# 1-Schematic_MicroCubeSat.net
KiCad netlist of a schematic drawn in EasyEDA
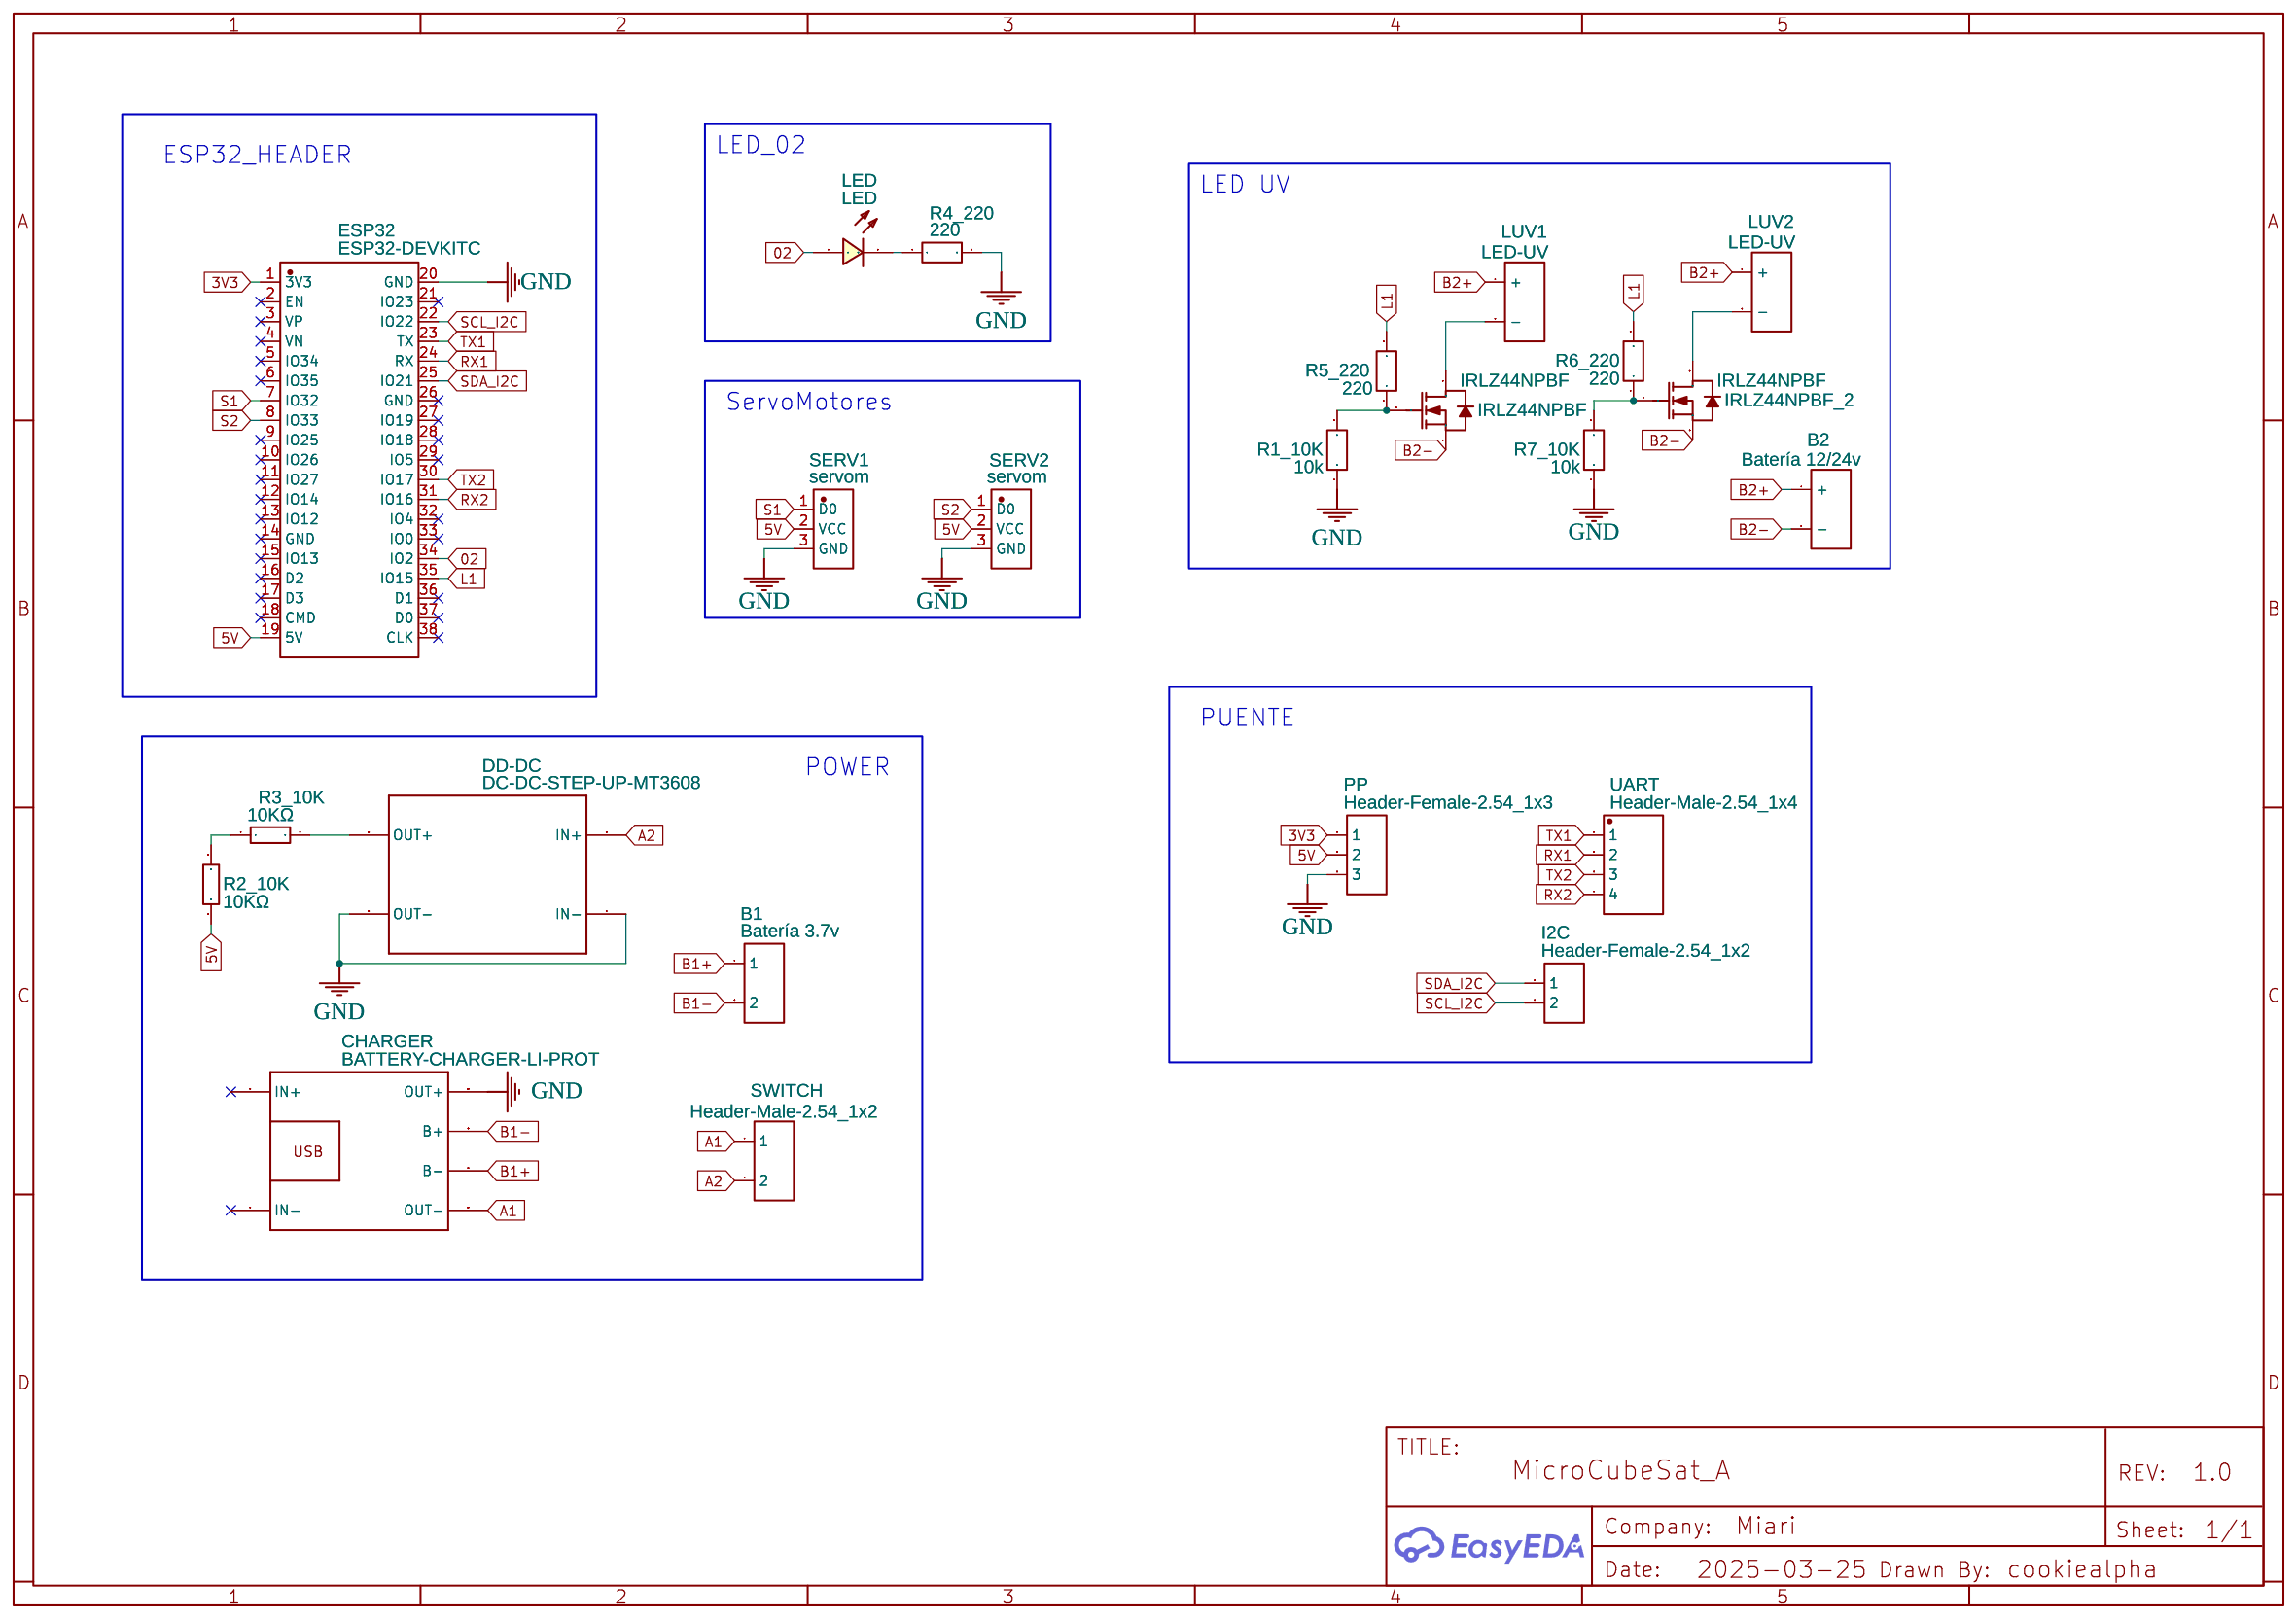
[diagram p0: schematic sheet]

(export (version "E")
  (design (tool "Eeschema 10.0.6"))
  (components
    (comp (ref "B1")
      (value "Batería 3.7v")
      (fields
        (field (name "Manufacturer Part") "826629-2")
        (field (name "Manufacturer") "TE Connectivity(泰科电子)")
      )
      (libsource (lib "") (part "Header-Male-2.54_1x2_1"))
    )
    (comp (ref "B2")
      (value "Batería 12/24v")
      (fields
        (field (name "Manufacturer Part") "826629-2")
        (field (name "Manufacturer") "TE Connectivity(泰科电子)")
      )
      (libsource (lib "") (part "Header-Male-2.54_1x2_2"))
    )
    (comp (ref "CHARGER")
      (value "BATTERY-CHARGER-LI-PROT")
      (libsource (lib "") (part "BATTERY-CHARGER-LI-PROT"))
    )
    (comp (ref "DD-DC") (value "DC-DC-STEP-UP-MT3608") (libsource (lib "") (part "DC-DC-STEP-UP-MT3608")))
    (comp (ref "ESP32")
      (value "ESP32-DEVKITC")
      (fields
        (field (name "Manufacturer Part") "ESP32-DevKitC")
        (field (name "Manufacturer") "ESPRESSIF(乐鑫)")
      )
      (libsource (lib "") (part "ESP32-DEVKITC"))
    )
    (comp (ref "I2C")
      (value "Header-Female-2.54_1x2")
      (fields (field (name "Manufacturer Part") "2.54-1*2P母") (field (name "Manufacturer") "BOOMELE(博穆精密)"))
      (libsource (lib "") (part "Header-Female-2.54_1x2"))
    )
    (comp (ref "IRLZ44NPBF")
      (value "IRLZ44NPBF")
      (fields (field (name "Manufacturer") "Infineon(英飞凌)"))
      (libsource (lib "") (part "IRLZ44NPBF_1"))
    )
    (comp (ref "IRLZ44NPBF_2")
      (value "IRLZ44NPBF")
      (fields (field (name "Manufacturer") "Infineon(英飞凌)"))
      (libsource (lib "") (part "IRLZ44NPBF"))
    )
    (comp (ref "LED")
      (value "LED")
      (fields (field (name "Manufacturer Part") "LED05-红灯"))
      (libsource (lib "") (part "LED05-红灯"))
    )
    (comp (ref "LUV1")
      (value "LED-UV")
      (fields
        (field (name "Manufacturer Part") "826629-2")
        (field (name "Manufacturer") "TE Connectivity(泰科电子)")
      )
      (libsource (lib "") (part "Header-Male-2.54_1x2"))
    )
    (comp (ref "LUV2")
      (value "LED-UV")
      (fields
        (field (name "Manufacturer Part") "826629-2")
        (field (name "Manufacturer") "TE Connectivity(泰科电子)")
      )
      (libsource (lib "") (part "Header-Male-2.54_1x2"))
    )
    (comp (ref "PP")
      (value "Header-Female-2.54_1x3")
      (fields (field (name "Manufacturer Part") "2.54-1*3P母") (field (name "Manufacturer") "BOOMELE(博穆精密)"))
      (libsource (lib "") (part "Header-Female-2.54_1x3"))
    )
    (comp (ref "R1_10K") (value "10k") (libsource (lib "") (part "ResistorAxial1/2wLHoles13.89mm_1")))
    (comp (ref "R2_10K")
      (value "10KΩ")
      (fields
        (field (name "Manufacturer Part") "MF58 103J3470")
        (field (name "Manufacturer") "Nanjing Shiheng Elec")
      )
      (libsource (lib "") (part "RESISTANCE_10k_1"))
    )
    (comp (ref "R3_10K")
      (value "10KΩ")
      (fields
        (field (name "Manufacturer Part") "MF58 103J3470")
        (field (name "Manufacturer") "Nanjing Shiheng Elec")
      )
      (libsource (lib "") (part "RESISTANCE_10k"))
    )
    (comp (ref "R4_220") (value "220") (libsource (lib "") (part "ResistorAxial1/2wLHoles13.89mm_4")))
    (comp (ref "R5_220") (value "220") (libsource (lib "") (part "ResistorAxial1/2wLHoles13.89mm_2")))
    (comp (ref "R6_220") (value "220") (libsource (lib "") (part "ResistorAxial1/2wLHoles13.89mm_3")))
    (comp (ref "R7_10K") (value "10k") (libsource (lib "") (part "ResistorAxial1/2wLHoles13.89mm")))
    (comp (ref "SERV1")
      (value "servom")
      (fields
        (field (name "Manufacturer Part") "HX PZ2.54-1x3P ZZ")
        (field (name "Manufacturer") "hanxia(韩下)")
      )
      (libsource (lib "") (part "HX PZ2.54-1X3P ZZ"))
    )
    (comp (ref "SERV2")
      (value "servom")
      (fields
        (field (name "Manufacturer Part") "HX PZ2.54-1x3P ZZ")
        (field (name "Manufacturer") "hanxia(韩下)")
      )
      (libsource (lib "") (part "HX PZ2.54-1X3P ZZ"))
    )
    (comp (ref "SWITCH")
      (value "Header-Male-2.54_1x2")
      (fields
        (field (name "Manufacturer Part") "826629-2")
        (field (name "Manufacturer") "TE Connectivity(泰科电子)")
      )
      (libsource (lib "") (part "Header-Male-2.54_1x2_3"))
    )
    (comp (ref "UART")
      (value "Header-Male-2.54_1x4")
      (fields (field (name "Manufacturer Part") "B-2100S04P-A110") (field (name "Manufacturer") "Ckmtw(灿科盟)"))
      (libsource (lib "") (part "Header-Male-2.54_1x4"))
    )
  )
  (nets
    (net (code "1") (name "02") (class "Default")
      (node (ref "ESP32") (pin "34") (pinfunction "IO2_34") (pintype "unspecified"))
      (node (ref "LED") (pin "1") (pinfunction "1_1") (pintype "unspecified"))
    )
    (net (code "2") (name "3V3") (class "Default")
      (node (ref "ESP32") (pin "1") (pinfunction "3V3_1") (pintype "unspecified"))
      (node (ref "PP") (pin "1") (pinfunction "1_1") (pintype "input"))
    )
    (net (code "3") (name "5V") (class "Default")
      (node (ref "ESP32") (pin "19") (pinfunction "5V_19") (pintype "unspecified"))
      (node (ref "PP") (pin "2") (pinfunction "2_2") (pintype "input"))
      (node (ref "R2_10K") (pin "1") (pinfunction "1_1") (pintype "unspecified"))
      (node (ref "SERV1") (pin "2") (pinfunction "VCC_2") (pintype "unspecified"))
      (node (ref "SERV2") (pin "2") (pinfunction "VCC_2") (pintype "unspecified"))
    )
    (net (code "4") (name "A1") (class "Default")
      (node (ref "CHARGER") (pin "OUT-") (pinfunction "OUT-_OUT-") (pintype "bidirectional"))
      (node (ref "SWITCH") (pin "1") (pinfunction "1_1") (pintype "unspecified"))
    )
    (net (code "5") (name "A2") (class "Default")
      (node (ref "DD-DC") (pin "IN+") (pinfunction "IN+_IN+") (pintype "bidirectional"))
      (node (ref "SWITCH") (pin "2") (pinfunction "2_2") (pintype "unspecified"))
    )
    (net (code "6") (name "B1+") (class "Default")
      (node (ref "B1") (pin "1") (pinfunction "1_1") (pintype "unspecified"))
      (node (ref "CHARGER") (pin "B-") (pinfunction "B-_B-") (pintype "bidirectional"))
    )
    (net (code "7") (name "B1-") (class "Default")
      (node (ref "B1") (pin "2") (pinfunction "2_2") (pintype "unspecified"))
      (node (ref "CHARGER") (pin "B+") (pinfunction "B+_B+") (pintype "bidirectional"))
    )
    (net (code "8") (name "B2+") (class "Default")
      (node (ref "B2") (pin "1") (pinfunction "+_1") (pintype "unspecified"))
      (node (ref "LUV1") (pin "1") (pinfunction "+_1") (pintype "unspecified"))
      (node (ref "LUV2") (pin "1") (pinfunction "+_1") (pintype "unspecified"))
    )
    (net (code "9") (name "B2-") (class "Default")
      (node (ref "B2") (pin "2") (pinfunction "-_2") (pintype "unspecified"))
      (node (ref "IRLZ44NPBF") (pin "3") (pinfunction "S_3") (pintype "unspecified"))
      (node (ref "IRLZ44NPBF_2") (pin "3") (pinfunction "S_3") (pintype "unspecified"))
    )
    (net (code "10") (name "GND") (class "Default")
      (node (ref "CHARGER") (pin "OUT+") (pinfunction "OUT+_OUT+") (pintype "bidirectional"))
      (node (ref "DD-DC") (pin "IN-") (pinfunction "IN-_IN-") (pintype "bidirectional"))
      (node (ref "DD-DC") (pin "OUT-") (pinfunction "OUT-_OUT-") (pintype "bidirectional"))
      (node (ref "ESP32") (pin "20") (pinfunction "GND_20") (pintype "unspecified"))
      (node (ref "PP") (pin "3") (pinfunction "3_3") (pintype "input"))
      (node (ref "R1_10K") (pin "1") (pinfunction "1_1") (pintype "unspecified"))
      (node (ref "R4_220") (pin "2") (pinfunction "2_2") (pintype "unspecified"))
      (node (ref "R7_10K") (pin "1") (pinfunction "1_1") (pintype "unspecified"))
      (node (ref "SERV1") (pin "3") (pinfunction "GND_3") (pintype "unspecified"))
      (node (ref "SERV2") (pin "3") (pinfunction "GND_3") (pintype "unspecified"))
    )
    (net (code "11") (name "L1") (class "Default")
      (node (ref "ESP32") (pin "35") (pinfunction "IO15_35") (pintype "unspecified"))
      (node (ref "R5_220") (pin "2") (pinfunction "2_2") (pintype "unspecified"))
      (node (ref "R6_220") (pin "2") (pinfunction "2_2") (pintype "unspecified"))
    )
    (net (code "12") (name "Net-(DD-DC-PadOUT+)") (class "Default")
      (node (ref "DD-DC") (pin "OUT+") (pinfunction "OUT+_OUT+") (pintype "bidirectional"))
      (node (ref "R3_10K") (pin "2") (pinfunction "2_2") (pintype "unspecified"))
    )
    (net (code "13") (name "Net-(IRLZ44NPBF-D)") (class "Default")
      (node (ref "IRLZ44NPBF") (pin "2") (pinfunction "D_2") (pintype "unspecified"))
      (node (ref "LUV1") (pin "2") (pinfunction "-_2") (pintype "unspecified"))
    )
    (net (code "14") (name "Net-(IRLZ44NPBF-G)") (class "Default")
      (node (ref "IRLZ44NPBF") (pin "1") (pinfunction "G_1") (pintype "unspecified"))
      (node (ref "R1_10K") (pin "2") (pinfunction "2_2") (pintype "unspecified"))
      (node (ref "R5_220") (pin "1") (pinfunction "1_1") (pintype "unspecified"))
    )
    (net (code "15") (name "Net-(IRLZ44NPBF_2-D)") (class "Default")
      (node (ref "IRLZ44NPBF_2") (pin "2") (pinfunction "D_2") (pintype "unspecified"))
      (node (ref "LUV2") (pin "2") (pinfunction "-_2") (pintype "unspecified"))
    )
    (net (code "16") (name "Net-(IRLZ44NPBF_2-G)") (class "Default")
      (node (ref "IRLZ44NPBF_2") (pin "1") (pinfunction "G_1") (pintype "unspecified"))
      (node (ref "R6_220") (pin "1") (pinfunction "1_1") (pintype "unspecified"))
      (node (ref "R7_10K") (pin "2") (pinfunction "2_2") (pintype "unspecified"))
    )
    (net (code "17") (name "Net-(LED-Pad2)") (class "Default")
      (node (ref "LED") (pin "2") (pinfunction "2_2") (pintype "unspecified"))
      (node (ref "R4_220") (pin "1") (pinfunction "1_1") (pintype "unspecified"))
    )
    (net (code "18") (name "Net-(R2_10K-Pad2)") (class "Default")
      (node (ref "R2_10K") (pin "2") (pinfunction "2_2") (pintype "unspecified"))
      (node (ref "R3_10K") (pin "1") (pinfunction "1_1") (pintype "unspecified"))
    )
    (net (code "19") (name "RX1") (class "Default")
      (node (ref "ESP32") (pin "24") (pinfunction "RX_24") (pintype "unspecified"))
      (node (ref "UART") (pin "2") (pinfunction "2_2") (pintype "unspecified"))
    )
    (net (code "20") (name "RX2") (class "Default")
      (node (ref "ESP32") (pin "31") (pinfunction "IO16_31") (pintype "unspecified"))
      (node (ref "UART") (pin "4") (pinfunction "4_4") (pintype "unspecified"))
    )
    (net (code "21") (name "S1") (class "Default")
      (node (ref "ESP32") (pin "7") (pinfunction "IO32_7") (pintype "unspecified"))
      (node (ref "SERV1") (pin "1") (pinfunction "D0_1") (pintype "unspecified"))
    )
    (net (code "22") (name "S2") (class "Default")
      (node (ref "ESP32") (pin "8") (pinfunction "IO33_8") (pintype "unspecified"))
      (node (ref "SERV2") (pin "1") (pinfunction "D0_1") (pintype "unspecified"))
    )
    (net (code "23") (name "SCL_I2C") (class "Default")
      (node (ref "ESP32") (pin "22") (pinfunction "IO22_22") (pintype "unspecified"))
      (node (ref "I2C") (pin "2") (pinfunction "2_2") (pintype "input"))
    )
    (net (code "24") (name "SDA_I2C") (class "Default")
      (node (ref "ESP32") (pin "25") (pinfunction "IO21_25") (pintype "unspecified"))
      (node (ref "I2C") (pin "1") (pinfunction "1_1") (pintype "input"))
    )
    (net (code "25") (name "TX1") (class "Default")
      (node (ref "ESP32") (pin "23") (pinfunction "TX_23") (pintype "unspecified"))
      (node (ref "UART") (pin "1") (pinfunction "1_1") (pintype "unspecified"))
    )
    (net (code "26") (name "TX2") (class "Default")
      (node (ref "ESP32") (pin "30") (pinfunction "IO17_30") (pintype "unspecified"))
      (node (ref "UART") (pin "3") (pinfunction "3_3") (pintype "unspecified"))
    )
    (net (code "27") (name "unconnected-(CHARGER-PadIN+)") (class "Default")
      (node (ref "CHARGER") (pin "IN+") (pinfunction "IN+_IN+") (pintype "bidirectional+no_connect"))
    )
    (net (code "28") (name "unconnected-(CHARGER-PadIN-)") (class "Default")
      (node (ref "CHARGER") (pin "IN-") (pinfunction "IN-_IN-") (pintype "bidirectional+no_connect"))
    )
    (net (code "29") (name "unconnected-(ESP32-CLK-Pad38)") (class "Default")
      (node (ref "ESP32") (pin "38") (pinfunction "CLK_38") (pintype "unspecified+no_connect"))
    )
    (net (code "30") (name "unconnected-(ESP32-CMD-Pad18)") (class "Default")
      (node (ref "ESP32") (pin "18") (pinfunction "CMD_18") (pintype "unspecified+no_connect"))
    )
    (net (code "31") (name "unconnected-(ESP32-D0-Pad37)") (class "Default")
      (node (ref "ESP32") (pin "37") (pinfunction "D0_37") (pintype "unspecified+no_connect"))
    )
    (net (code "32") (name "unconnected-(ESP32-D1-Pad36)") (class "Default")
      (node (ref "ESP32") (pin "36") (pinfunction "D1_36") (pintype "unspecified+no_connect"))
    )
    (net (code "33") (name "unconnected-(ESP32-D2-Pad16)") (class "Default")
      (node (ref "ESP32") (pin "16") (pinfunction "D2_16") (pintype "unspecified+no_connect"))
    )
    (net (code "34") (name "unconnected-(ESP32-D3-Pad17)") (class "Default")
      (node (ref "ESP32") (pin "17") (pinfunction "D3_17") (pintype "unspecified+no_connect"))
    )
    (net (code "35") (name "unconnected-(ESP32-EN-Pad2)") (class "Default")
      (node (ref "ESP32") (pin "2") (pinfunction "EN_2") (pintype "unspecified+no_connect"))
    )
    (net (code "36") (name "unconnected-(ESP32-GND-Pad14)") (class "Default")
      (node (ref "ESP32") (pin "14") (pinfunction "GND_14") (pintype "unspecified+no_connect"))
    )
    (net (code "37") (name "unconnected-(ESP32-GND-Pad26)") (class "Default")
      (node (ref "ESP32") (pin "26") (pinfunction "GND_26") (pintype "unspecified+no_connect"))
    )
    (net (code "38") (name "unconnected-(ESP32-IO0-Pad33)") (class "Default")
      (node (ref "ESP32") (pin "33") (pinfunction "IO0_33") (pintype "unspecified+no_connect"))
    )
    (net (code "39") (name "unconnected-(ESP32-IO4-Pad32)") (class "Default")
      (node (ref "ESP32") (pin "32") (pinfunction "IO4_32") (pintype "unspecified+no_connect"))
    )
    (net (code "40") (name "unconnected-(ESP32-IO5-Pad29)") (class "Default")
      (node (ref "ESP32") (pin "29") (pinfunction "IO5_29") (pintype "unspecified+no_connect"))
    )
    (net (code "41") (name "unconnected-(ESP32-IO12-Pad13)") (class "Default")
      (node (ref "ESP32") (pin "13") (pinfunction "IO12_13") (pintype "unspecified+no_connect"))
    )
    (net (code "42") (name "unconnected-(ESP32-IO13-Pad15)") (class "Default")
      (node (ref "ESP32") (pin "15") (pinfunction "IO13_15") (pintype "unspecified+no_connect"))
    )
    (net (code "43") (name "unconnected-(ESP32-IO14-Pad12)") (class "Default")
      (node (ref "ESP32") (pin "12") (pinfunction "IO14_12") (pintype "unspecified+no_connect"))
    )
    (net (code "44") (name "unconnected-(ESP32-IO18-Pad28)") (class "Default")
      (node (ref "ESP32") (pin "28") (pinfunction "IO18_28") (pintype "unspecified+no_connect"))
    )
    (net (code "45") (name "unconnected-(ESP32-IO19-Pad27)") (class "Default")
      (node (ref "ESP32") (pin "27") (pinfunction "IO19_27") (pintype "unspecified+no_connect"))
    )
    (net (code "46") (name "unconnected-(ESP32-IO23-Pad21)") (class "Default")
      (node (ref "ESP32") (pin "21") (pinfunction "IO23_21") (pintype "unspecified+no_connect"))
    )
    (net (code "47") (name "unconnected-(ESP32-IO25-Pad9)") (class "Default")
      (node (ref "ESP32") (pin "9") (pinfunction "IO25_9") (pintype "unspecified+no_connect"))
    )
    (net (code "48") (name "unconnected-(ESP32-IO26-Pad10)") (class "Default")
      (node (ref "ESP32") (pin "10") (pinfunction "IO26_10") (pintype "unspecified+no_connect"))
    )
    (net (code "49") (name "unconnected-(ESP32-IO27-Pad11)") (class "Default")
      (node (ref "ESP32") (pin "11") (pinfunction "IO27_11") (pintype "unspecified+no_connect"))
    )
    (net (code "50") (name "unconnected-(ESP32-IO34-Pad5)") (class "Default")
      (node (ref "ESP32") (pin "5") (pinfunction "IO34_5") (pintype "unspecified+no_connect"))
    )
    (net (code "51") (name "unconnected-(ESP32-IO35-Pad6)") (class "Default")
      (node (ref "ESP32") (pin "6") (pinfunction "IO35_6") (pintype "unspecified+no_connect"))
    )
    (net (code "52") (name "unconnected-(ESP32-VN-Pad4)") (class "Default")
      (node (ref "ESP32") (pin "4") (pinfunction "VN_4") (pintype "unspecified+no_connect"))
    )
    (net (code "53") (name "unconnected-(ESP32-VP-Pad3)") (class "Default")
      (node (ref "ESP32") (pin "3") (pinfunction "VP_3") (pintype "unspecified+no_connect"))
    )
  )
)
